# power.net
KiCad netlist of a schematic drawn in Altium Designer
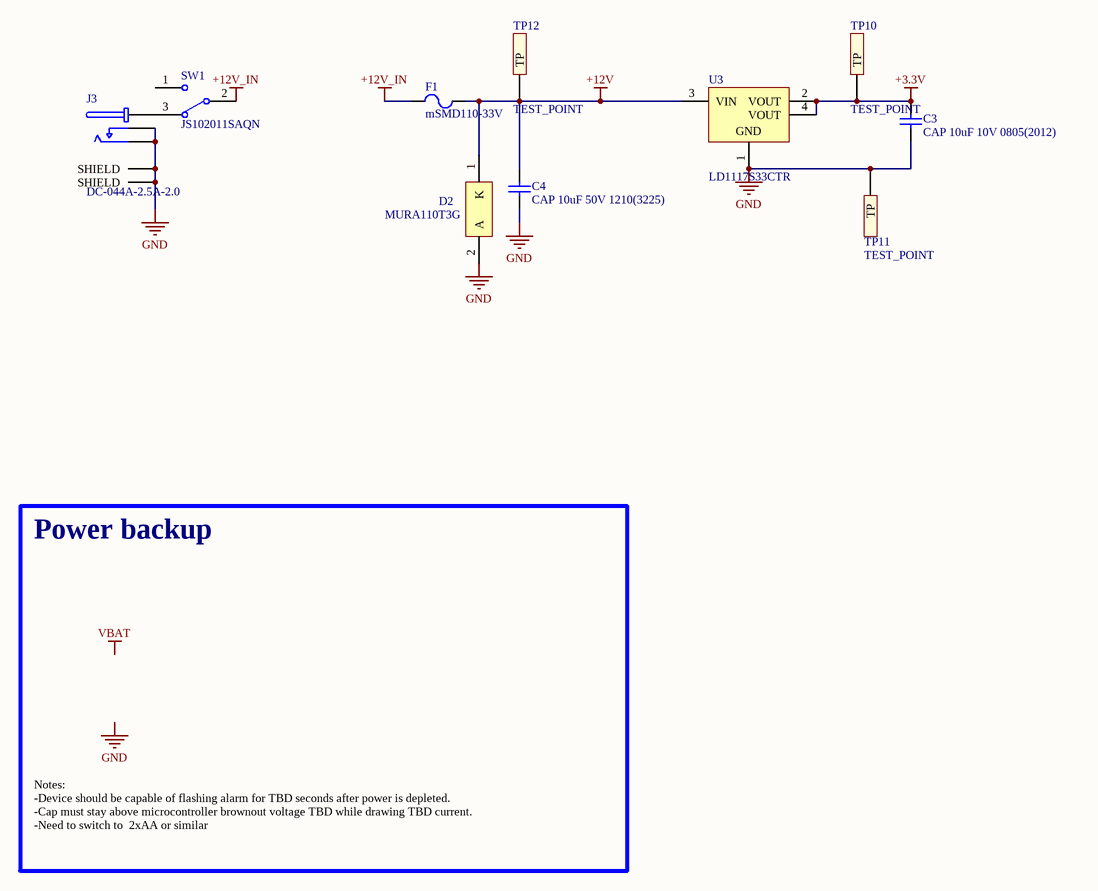
[diagram p0: power.SchDoc]

(export (version "E")
  (design (tool "Eeschema 10.0.6"))
  (components
    (comp (ref "C3")
      (value "CAP 10uF 10V 0805(2012)")
      (footprint "CAPC0805(2012)145_N")
      (description "CAP 10uF 10V ±10% 0805 (2012 Metric) Thickness 1.45mm SMD")
      (fields (field (name "TOLERANCE") "Â±10%"))
      (libsource (lib "Altium Content Vault") (part "CAP"))
    )
    (comp (ref "C4")
      (value "CAP 10uF 50V 1210(3225)")
      (footprint "CAPC1210(3225)190_N")
      (description "CAP 10uF 50V -20% to +80% 1210 (3225 Metric) Thickness 1.9mm SMD")
      (fields (field (name "TOLERANCE") "-20% to +80%"))
      (libsource (lib "Altium Content Vault") (part "CAP"))
    )
    (comp (ref "D2")
      (value "MURA110T3G")
      (footprint "ONSC-SMA-2-403D-02_V")
      (description "Surface Mount Ultrafast Power Rectifier, 2-Pin SMA, Pb-Free, Tape and Reel")
      (fields (field (name "MANUFACTURER") "On Semiconductor"))
      (libsource (lib "Altium Content Vault") (part "ONSC-D-K1A2-2_A"))
    )
    (comp (ref "F1")
      (value "mSMD110-33V")
      (footprint "SEAANDLAND_1812")
      (description "Surface Mount Fuses 33V 100A 1.1A 2.2A 1812 RoHS")
      (fields (field (name "MANUFACTURER") "Sea & Land Electronic Corp"))
      (libsource (lib "Blinkinlabs") (part "mSMD110-33V"))
    )
    (comp (ref "J3")
      (value "DC-044A-2.5A-2.0")
      (footprint "DC-044A-2.5A-2.0")
      (description "DC Jack, 6mm OD, 2mm ID")
      (fields (field (name "MANUFACTURER") "XKB"))
      (libsource (lib "Blinkinlabs") (part "DC-044A-2.5A-2.0"))
    )
    (comp (ref "SW1")
      (value "JS102011SAQN")
      (footprint "CKCP-JS102011SAQN-3_V")
      (description "Sub-Miniature Slide Switch, SPDT, -40 to 85 degC, 3-Pin SMD, RoHS, Tape and Reel")
      (fields (field (name "MANUFACTURER") "C&K Components"))
      (libsource (lib "Altium Content Vault") (part "SW-SPDT-3"))
    )
    (comp (ref "TP10")
      (value "TEST_POINT")
      (footprint "TP-SMD-1mm")
      (description "Test point")
      (libsource (lib "Blinkinlabs") (part "TEST_POINT"))
    )
    (comp (ref "TP11")
      (value "TEST_POINT")
      (footprint "TP-SMD-1mm")
      (description "Test point")
      (libsource (lib "") (part "TEST_POINT_1"))
    )
    (comp (ref "TP12")
      (value "TEST_POINT")
      (footprint "TP-SMD-1mm")
      (description "Test point")
      (libsource (lib "Blinkinlabs") (part "TEST_POINT"))
    )
    (comp (ref "U3")
      (value "LD1117S33CTR")
      (footprint "SOT-223_N")
      (description "Fixed Low Drop Positive Voltage Regulator, 3.3V, 4-Pin SOT-223, Tape and Reel")
      (libsource (lib "Altium Content Vault") (part "PM-REG-LD1117-SOT4"))
    )
  )
  (nets
    (net (code "1") (name "+3.3V") (class "Default")
      (node (ref "C3") (pin "2") (pinfunction "2_2") (pintype "passive"))
      (node (ref "TP10") (pin "1") (pinfunction "TP_1") (pintype "passive"))
      (node (ref "U3") (pin "2") (pinfunction "VOUT_2") (pintype "power_in"))
      (node (ref "U3") (pin "4") (pinfunction "VOUT_4") (pintype "power_in"))
    )
    (net (code "2") (name "+12V") (class "Default")
      (node (ref "C4") (pin "2") (pinfunction "2_2") (pintype "passive"))
      (node (ref "D2") (pin "1") (pinfunction "K_1") (pintype "passive"))
      (node (ref "F1") (pin "2") (pinfunction "2_2") (pintype "passive"))
      (node (ref "TP12") (pin "1") (pinfunction "TP_1") (pintype "passive"))
      (node (ref "U3") (pin "3") (pinfunction "VIN_3") (pintype "power_in"))
    )
    (net (code "3") (name "+12V_IN") (class "Default")
      (node (ref "F1") (pin "1") (pinfunction "1_1") (pintype "passive"))
      (node (ref "SW1") (pin "2") (pinfunction "2_2") (pintype "passive"))
    )
    (net (code "4") (name "GND") (class "Default")
      (node (ref "C3") (pin "1") (pinfunction "1_1") (pintype "passive"))
      (node (ref "C4") (pin "1") (pinfunction "1_1") (pintype "passive"))
      (node (ref "D2") (pin "2") (pinfunction "A_2") (pintype "passive"))
      (node (ref "J3") (pin "2") (pinfunction "2_2") (pintype "passive"))
      (node (ref "J3") (pin "3") (pinfunction "3_3") (pintype "passive"))
      (node (ref "J3") (pin "4") (pinfunction "SHIELD_4") (pintype "passive"))
      (node (ref "J3") (pin "5") (pinfunction "SHIELD_5") (pintype "passive"))
      (node (ref "TP11") (pin "1") (pinfunction "TP_1") (pintype "passive"))
      (node (ref "U3") (pin "1") (pinfunction "GND_1") (pintype "power_in"))
    )
    (net (code "5") (name "Net-(J3-Pad1)") (class "Default")
      (node (ref "J3") (pin "1") (pinfunction "1_1") (pintype "passive"))
      (node (ref "SW1") (pin "3") (pinfunction "3_3") (pintype "passive"))
    )
    (net (code "7") (name "unconnected-(SW1-Pad1)") (class "Default")
      (node (ref "SW1") (pin "1") (pinfunction "1_1") (pintype "passive"))
    )
  )
)
